# FPGA_PWR.net
KiCad netlist of a schematic drawn in Altium Designer
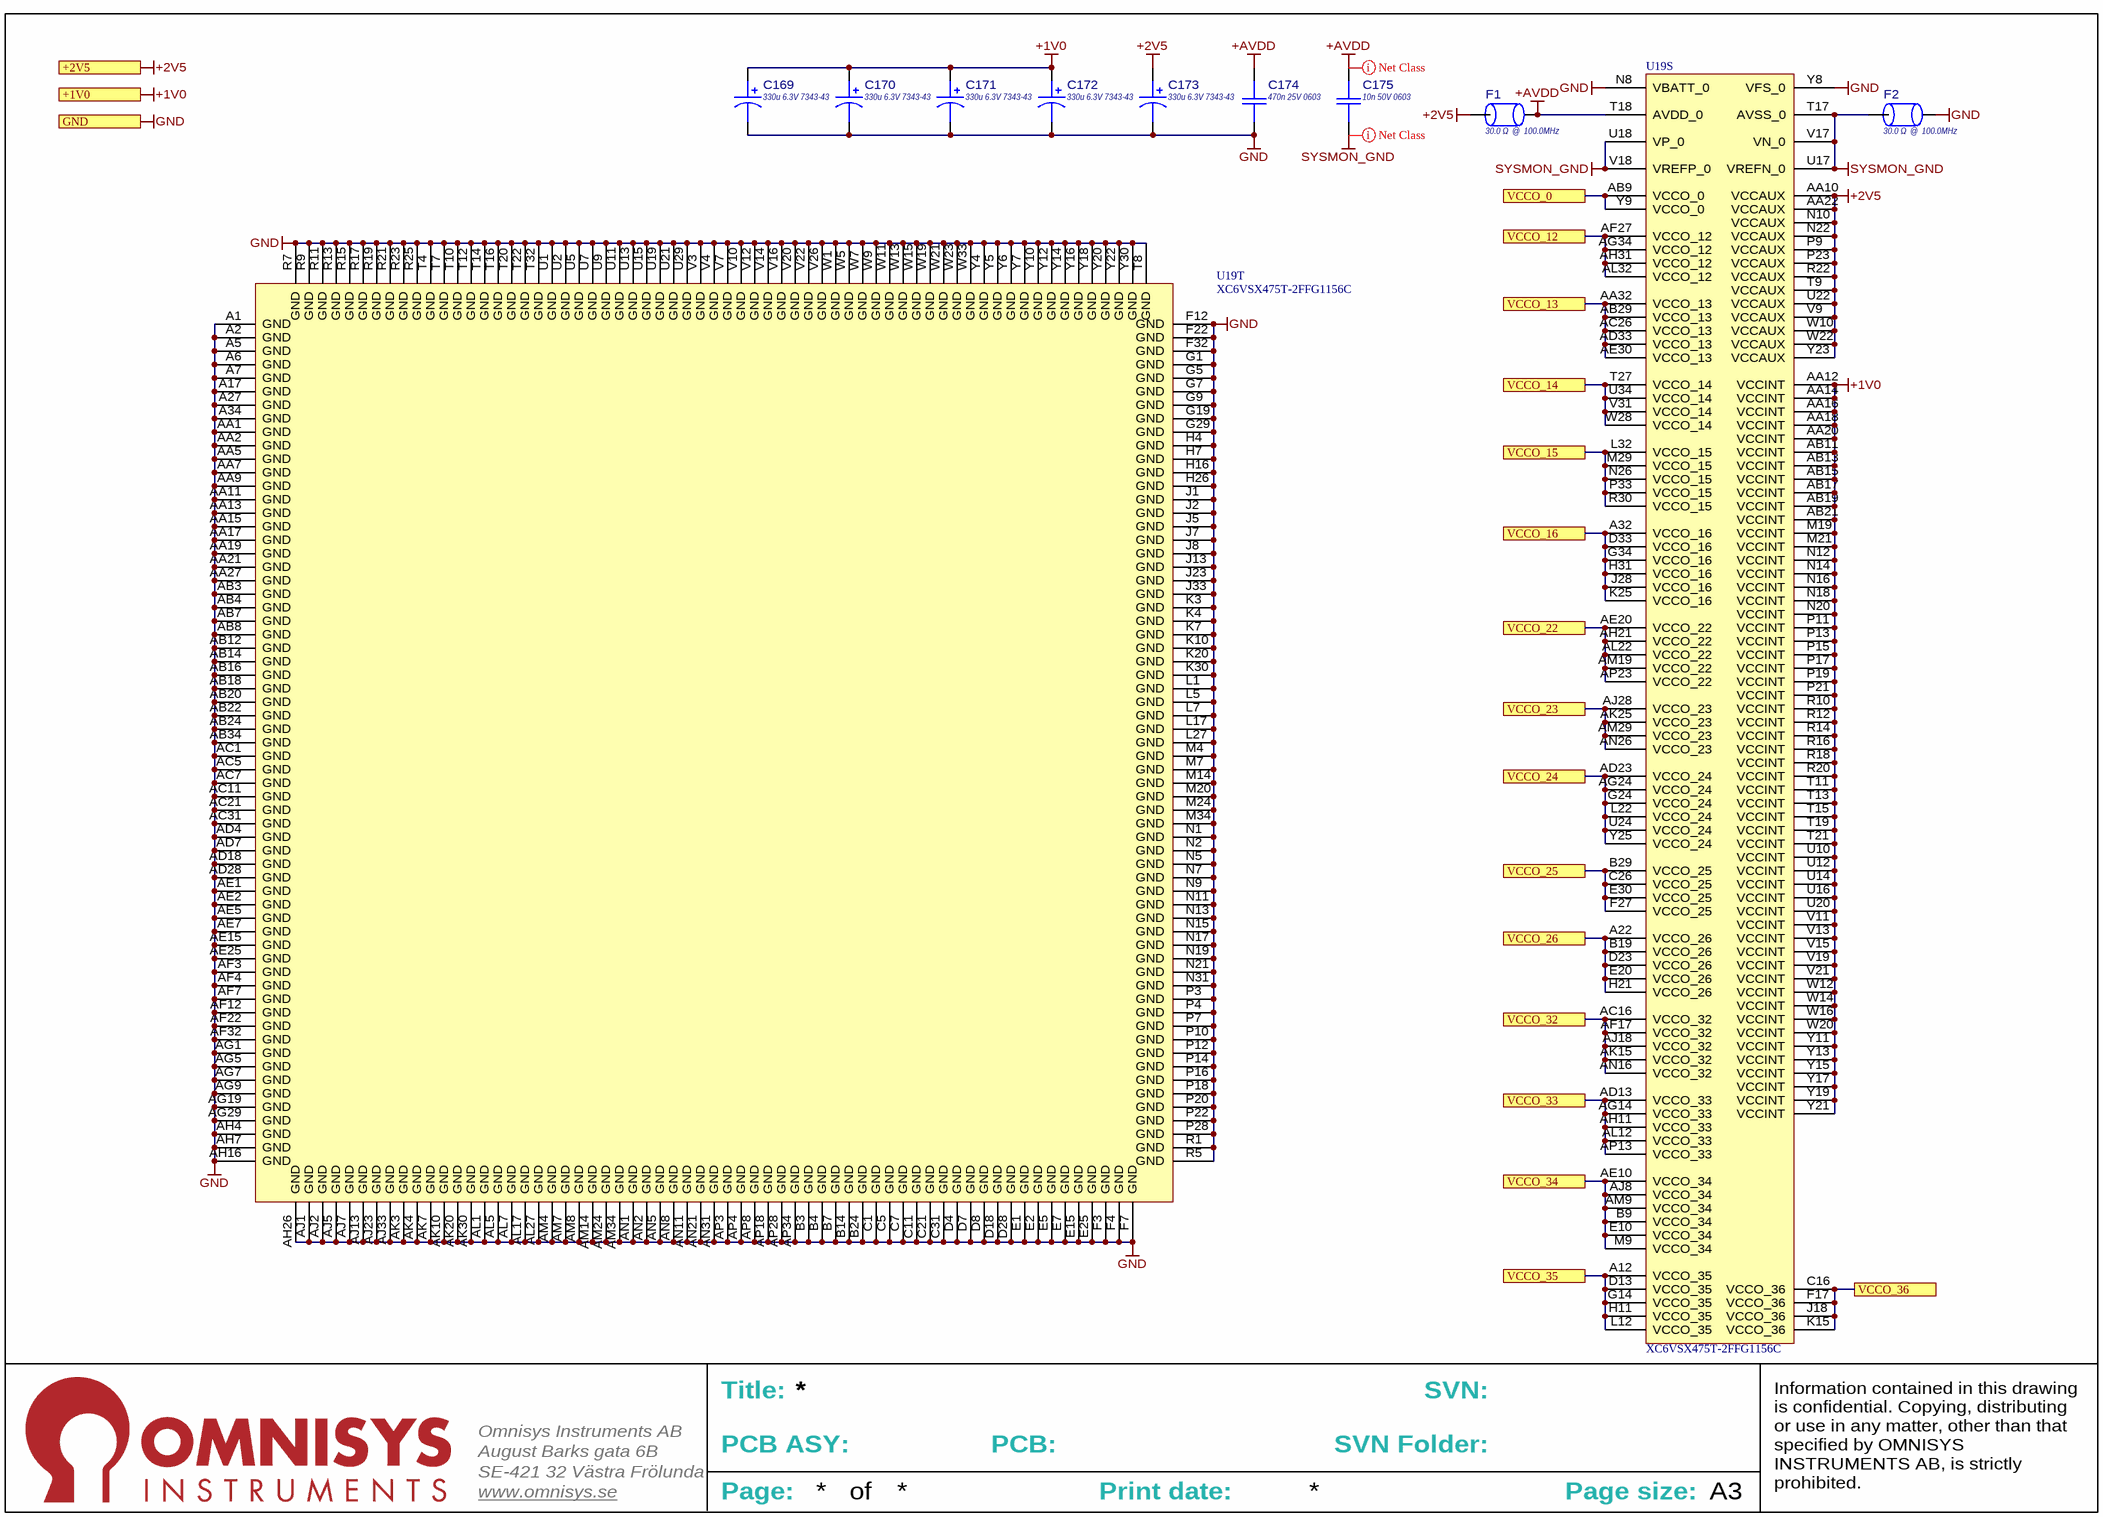
[diagram p0: FPGA_PWR.SchDoc]

(export (version "E")
  (design (tool "Eeschema 10.0.6"))
  (components
    (comp (ref "C169")
      (value "330u 6.3V 7343-43")
      (footprint "CAPMP7343X43N")
      (fields (field (name "PARTNUMBER") "NOJE337M006RWJ") (field (name "TOLERANCE") "±20%"))
      (libsource (lib "Omnisys Vault") (part "CAP-2PIN-POL"))
    )
    (comp (ref "C170")
      (value "330u 6.3V 7343-43")
      (footprint "CAPMP7343X43N")
      (fields (field (name "PARTNUMBER") "NOJE337M006RWJ") (field (name "TOLERANCE") "±20%"))
      (libsource (lib "Omnisys Vault") (part "CAP-2PIN-POL"))
    )
    (comp (ref "C171")
      (value "330u 6.3V 7343-43")
      (footprint "CAPMP7343X43N")
      (fields (field (name "PARTNUMBER") "NOJE337M006RWJ") (field (name "TOLERANCE") "±20%"))
      (libsource (lib "Omnisys Vault") (part "CAP-2PIN-POL"))
    )
    (comp (ref "C172")
      (value "330u 6.3V 7343-43")
      (footprint "CAPMP7343X43N")
      (fields (field (name "PARTNUMBER") "NOJE337M006RWJ") (field (name "TOLERANCE") "±20%"))
      (libsource (lib "Omnisys Vault") (part "CAP-2PIN-POL"))
    )
    (comp (ref "C173")
      (value "330u 6.3V 7343-43")
      (footprint "CAPMP7343X43N")
      (fields (field (name "PARTNUMBER") "NOJE337M006RWJ") (field (name "TOLERANCE") "±20%"))
      (libsource (lib "Omnisys Vault") (part "CAP-2PIN-POL"))
    )
    (comp (ref "C174")
      (value "470n 25V 0603")
      (footprint "CAPC1608X90N")
      (description "470n 25V X7R ±10% 0603 (1608 metric)")
      (fields (field (name "PARTNUMBER") "GRM188R71E474KA12") (field (name "TOLERANCE") "±10%"))
      (libsource (lib "Omnisys Vault") (part "CAP-2PIN"))
    )
    (comp (ref "C175")
      (value "10n 50V 0603")
      (footprint "CAPC1608X90N")
      (description "10n 50V X7R ±5% 0603 (1608 metric)")
      (fields (field (name "PARTNUMBER") "GRM188R71H103JA01") (field (name "TOLERANCE") "±5%"))
      (libsource (lib "Omnisys Vault") (part "CAP-2PIN"))
    )
    (comp (ref "F1")
      (value "30.0 Ω  @  100.0MHz")
      (footprint "INDC2012X11L")
      (description "Ferrite bead, Würth Elektronik WE-CBF 2012 (0805), 74279206 ,  30.0 Ω  @  100.0MHz")
      (fields (field (name "PARTNUMBER") "74279206"))
      (libsource (lib "Omnisys Vault") (part "BEAD-2PIN"))
    )
    (comp (ref "F2")
      (value "30.0 Ω  @  100.0MHz")
      (footprint "INDC2012X11L")
      (description "Ferrite bead, Würth Elektronik WE-CBF 2012 (0805), 74279206 ,  30.0 Ω  @  100.0MHz")
      (fields (field (name "PARTNUMBER") "74279206"))
      (libsource (lib "Omnisys Vault") (part "BEAD-2PIN"))
    )
    (comp (ref "U19")
      (value "XC6VSX475T-2FFG1156C")
      (footprint "FFG1156")
      (libsource (lib "Altium Content Vault") (part "FPGA-XVR6-XC6VXXXXXT-GA1156"))
    )
  )
  (nets
    (net (code "1") (name "+1V0") (class "Default")
      (node (ref "C169") (pin "1") (pinfunction "1_1") (pintype "passive"))
      (node (ref "C170") (pin "1") (pinfunction "1_1") (pintype "passive"))
      (node (ref "C171") (pin "1") (pinfunction "1_1") (pintype "passive"))
      (node (ref "C172") (pin "1") (pinfunction "1_1") (pintype "passive"))
      (node (ref "U19") (pin "AA12") (pinfunction "VCCINT_AA12") (pintype "power_in"))
      (node (ref "U19") (pin "AA14") (pinfunction "VCCINT_AA14") (pintype "power_in"))
      (node (ref "U19") (pin "AA16") (pinfunction "VCCINT_AA16") (pintype "power_in"))
      (node (ref "U19") (pin "AA18") (pinfunction "VCCINT_AA18") (pintype "power_in"))
      (node (ref "U19") (pin "AA20") (pinfunction "VCCINT_AA20") (pintype "power_in"))
      (node (ref "U19") (pin "AB11") (pinfunction "VCCINT_AB11") (pintype "power_in"))
      (node (ref "U19") (pin "AB13") (pinfunction "VCCINT_AB13") (pintype "power_in"))
      (node (ref "U19") (pin "AB15") (pinfunction "VCCINT_AB15") (pintype "power_in"))
      (node (ref "U19") (pin "AB17") (pinfunction "VCCINT_AB17") (pintype "power_in"))
      (node (ref "U19") (pin "AB19") (pinfunction "VCCINT_AB19") (pintype "power_in"))
      (node (ref "U19") (pin "AB21") (pinfunction "VCCINT_AB21") (pintype "power_in"))
      (node (ref "U19") (pin "M19") (pinfunction "VCCINT_M19") (pintype "power_in"))
      (node (ref "U19") (pin "M21") (pinfunction "VCCINT_M21") (pintype "power_in"))
      (node (ref "U19") (pin "N12") (pinfunction "VCCINT_N12") (pintype "power_in"))
      (node (ref "U19") (pin "N14") (pinfunction "VCCINT_N14") (pintype "power_in"))
      (node (ref "U19") (pin "N16") (pinfunction "VCCINT_N16") (pintype "power_in"))
      (node (ref "U19") (pin "N18") (pinfunction "VCCINT_N18") (pintype "power_in"))
      (node (ref "U19") (pin "N20") (pinfunction "VCCINT_N20") (pintype "power_in"))
      (node (ref "U19") (pin "P11") (pinfunction "VCCINT_P11") (pintype "power_in"))
      (node (ref "U19") (pin "P13") (pinfunction "VCCINT_P13") (pintype "power_in"))
      (node (ref "U19") (pin "P15") (pinfunction "VCCINT_P15") (pintype "power_in"))
      (node (ref "U19") (pin "P17") (pinfunction "VCCINT_P17") (pintype "power_in"))
      (node (ref "U19") (pin "P19") (pinfunction "VCCINT_P19") (pintype "power_in"))
      (node (ref "U19") (pin "P21") (pinfunction "VCCINT_P21") (pintype "power_in"))
      (node (ref "U19") (pin "R10") (pinfunction "VCCINT_R10") (pintype "power_in"))
      (node (ref "U19") (pin "R12") (pinfunction "VCCINT_R12") (pintype "power_in"))
      (node (ref "U19") (pin "R14") (pinfunction "VCCINT_R14") (pintype "power_in"))
      (node (ref "U19") (pin "R16") (pinfunction "VCCINT_R16") (pintype "power_in"))
      (node (ref "U19") (pin "R18") (pinfunction "VCCINT_R18") (pintype "power_in"))
      (node (ref "U19") (pin "R20") (pinfunction "VCCINT_R20") (pintype "power_in"))
      (node (ref "U19") (pin "T11") (pinfunction "VCCINT_T11") (pintype "power_in"))
      (node (ref "U19") (pin "T13") (pinfunction "VCCINT_T13") (pintype "power_in"))
      (node (ref "U19") (pin "T15") (pinfunction "VCCINT_T15") (pintype "power_in"))
      (node (ref "U19") (pin "T19") (pinfunction "VCCINT_T19") (pintype "power_in"))
      (node (ref "U19") (pin "T21") (pinfunction "VCCINT_T21") (pintype "power_in"))
      (node (ref "U19") (pin "U10") (pinfunction "VCCINT_U10") (pintype "power_in"))
      (node (ref "U19") (pin "U12") (pinfunction "VCCINT_U12") (pintype "power_in"))
      (node (ref "U19") (pin "U14") (pinfunction "VCCINT_U14") (pintype "power_in"))
      (node (ref "U19") (pin "U16") (pinfunction "VCCINT_U16") (pintype "power_in"))
      (node (ref "U19") (pin "U20") (pinfunction "VCCINT_U20") (pintype "power_in"))
      (node (ref "U19") (pin "V11") (pinfunction "VCCINT_V11") (pintype "power_in"))
      (node (ref "U19") (pin "V13") (pinfunction "VCCINT_V13") (pintype "power_in"))
      (node (ref "U19") (pin "V15") (pinfunction "VCCINT_V15") (pintype "power_in"))
      (node (ref "U19") (pin "V19") (pinfunction "VCCINT_V19") (pintype "power_in"))
      (node (ref "U19") (pin "V21") (pinfunction "VCCINT_V21") (pintype "power_in"))
      (node (ref "U19") (pin "W12") (pinfunction "VCCINT_W12") (pintype "power_in"))
      (node (ref "U19") (pin "W14") (pinfunction "VCCINT_W14") (pintype "power_in"))
      (node (ref "U19") (pin "W16") (pinfunction "VCCINT_W16") (pintype "power_in"))
      (node (ref "U19") (pin "W20") (pinfunction "VCCINT_W20") (pintype "power_in"))
      (node (ref "U19") (pin "Y11") (pinfunction "VCCINT_Y11") (pintype "power_in"))
      (node (ref "U19") (pin "Y13") (pinfunction "VCCINT_Y13") (pintype "power_in"))
      (node (ref "U19") (pin "Y15") (pinfunction "VCCINT_Y15") (pintype "power_in"))
      (node (ref "U19") (pin "Y17") (pinfunction "VCCINT_Y17") (pintype "power_in"))
      (node (ref "U19") (pin "Y19") (pinfunction "VCCINT_Y19") (pintype "power_in"))
      (node (ref "U19") (pin "Y21") (pinfunction "VCCINT_Y21") (pintype "power_in"))
    )
    (net (code "2") (name "+2V5") (class "Default")
      (node (ref "C173") (pin "1") (pinfunction "1_1") (pintype "passive"))
      (node (ref "F1") (pin "1") (pinfunction "1_1") (pintype "passive"))
      (node (ref "U19") (pin "AA10") (pinfunction "VCCAUX_AA10") (pintype "power_in"))
      (node (ref "U19") (pin "AA22") (pinfunction "VCCAUX_AA22") (pintype "power_in"))
      (node (ref "U19") (pin "N10") (pinfunction "VCCAUX_N10") (pintype "power_in"))
      (node (ref "U19") (pin "N22") (pinfunction "VCCAUX_N22") (pintype "power_in"))
      (node (ref "U19") (pin "P23") (pinfunction "VCCAUX_P23") (pintype "power_in"))
      (node (ref "U19") (pin "P9") (pinfunction "VCCAUX_P9") (pintype "power_in"))
      (node (ref "U19") (pin "R22") (pinfunction "VCCAUX_R22") (pintype "power_in"))
      (node (ref "U19") (pin "T9") (pinfunction "VCCAUX_T9") (pintype "power_in"))
      (node (ref "U19") (pin "U22") (pinfunction "VCCAUX_U22") (pintype "power_in"))
      (node (ref "U19") (pin "V9") (pinfunction "VCCAUX_V9") (pintype "power_in"))
      (node (ref "U19") (pin "W10") (pinfunction "VCCAUX_W10") (pintype "power_in"))
      (node (ref "U19") (pin "W22") (pinfunction "VCCAUX_W22") (pintype "power_in"))
      (node (ref "U19") (pin "Y23") (pinfunction "VCCAUX_Y23") (pintype "power_in"))
    )
    (net (code "3") (name "+AVDD") (class "Default")
      (node (ref "C174") (pin "1") (pinfunction "1_1") (pintype "passive"))
      (node (ref "C175") (pin "1") (pinfunction "1_1") (pintype "passive"))
      (node (ref "F1") (pin "2") (pinfunction "2_2") (pintype "passive"))
      (node (ref "U19") (pin "T18") (pinfunction "AVDD_0_T18") (pintype "power_in"))
    )
    (net (code "4") (name "/VCCO_0") (class "Default")
      (node (ref "U19") (pin "AB9") (pinfunction "VCCO_0_AB9") (pintype "power_in"))
      (node (ref "U19") (pin "Y9") (pinfunction "VCCO_0_Y9") (pintype "power_in"))
    )
    (net (code "5") (name "/VCCO_12") (class "Default")
      (node (ref "U19") (pin "AF27") (pinfunction "VCCO_12_AF27") (pintype "power_in"))
      (node (ref "U19") (pin "AG34") (pinfunction "VCCO_12_AG34") (pintype "power_in"))
      (node (ref "U19") (pin "AH31") (pinfunction "VCCO_12_AH31") (pintype "power_in"))
      (node (ref "U19") (pin "AL32") (pinfunction "VCCO_12_AL32") (pintype "power_in"))
    )
    (net (code "6") (name "/VCCO_13") (class "Default")
      (node (ref "U19") (pin "AA32") (pinfunction "VCCO_13_AA32") (pintype "power_in"))
      (node (ref "U19") (pin "AB29") (pinfunction "VCCO_13_AB29") (pintype "power_in"))
      (node (ref "U19") (pin "AC26") (pinfunction "VCCO_13_AC26") (pintype "power_in"))
      (node (ref "U19") (pin "AD33") (pinfunction "VCCO_13_AD33") (pintype "power_in"))
      (node (ref "U19") (pin "AE30") (pinfunction "VCCO_13_AE30") (pintype "power_in"))
    )
    (net (code "7") (name "/VCCO_14") (class "Default")
      (node (ref "U19") (pin "T27") (pinfunction "VCCO_14_T27") (pintype "power_in"))
      (node (ref "U19") (pin "U34") (pinfunction "VCCO_14_U34") (pintype "power_in"))
      (node (ref "U19") (pin "V31") (pinfunction "VCCO_14_V31") (pintype "power_in"))
      (node (ref "U19") (pin "W28") (pinfunction "VCCO_14_W28") (pintype "power_in"))
    )
    (net (code "8") (name "/VCCO_15") (class "Default")
      (node (ref "U19") (pin "L32") (pinfunction "VCCO_15_L32") (pintype "power_in"))
      (node (ref "U19") (pin "M29") (pinfunction "VCCO_15_M29") (pintype "power_in"))
      (node (ref "U19") (pin "N26") (pinfunction "VCCO_15_N26") (pintype "power_in"))
      (node (ref "U19") (pin "P33") (pinfunction "VCCO_15_P33") (pintype "power_in"))
      (node (ref "U19") (pin "R30") (pinfunction "VCCO_15_R30") (pintype "power_in"))
    )
    (net (code "9") (name "/VCCO_16") (class "Default")
      (node (ref "U19") (pin "A32") (pinfunction "VCCO_16_A32") (pintype "power_in"))
      (node (ref "U19") (pin "D33") (pinfunction "VCCO_16_D33") (pintype "power_in"))
      (node (ref "U19") (pin "G34") (pinfunction "VCCO_16_G34") (pintype "power_in"))
      (node (ref "U19") (pin "H31") (pinfunction "VCCO_16_H31") (pintype "power_in"))
      (node (ref "U19") (pin "J28") (pinfunction "VCCO_16_J28") (pintype "power_in"))
      (node (ref "U19") (pin "K25") (pinfunction "VCCO_16_K25") (pintype "power_in"))
    )
    (net (code "10") (name "/VCCO_22") (class "Default")
      (node (ref "U19") (pin "AE20") (pinfunction "VCCO_22_AE20") (pintype "power_in"))
      (node (ref "U19") (pin "AH21") (pinfunction "VCCO_22_AH21") (pintype "power_in"))
      (node (ref "U19") (pin "AL22") (pinfunction "VCCO_22_AL22") (pintype "power_in"))
      (node (ref "U19") (pin "AM19") (pinfunction "VCCO_22_AM19") (pintype "power_in"))
      (node (ref "U19") (pin "AP23") (pinfunction "VCCO_22_AP23") (pintype "power_in"))
    )
    (net (code "11") (name "/VCCO_23") (class "Default")
      (node (ref "U19") (pin "AJ28") (pinfunction "VCCO_23_AJ28") (pintype "power_in"))
      (node (ref "U19") (pin "AK25") (pinfunction "VCCO_23_AK25") (pintype "power_in"))
      (node (ref "U19") (pin "AM29") (pinfunction "VCCO_23_AM29") (pintype "power_in"))
      (node (ref "U19") (pin "AN26") (pinfunction "VCCO_23_AN26") (pintype "power_in"))
    )
    (net (code "12") (name "/VCCO_24") (class "Default")
      (node (ref "U19") (pin "AD23") (pinfunction "VCCO_24_AD23") (pintype "power_in"))
      (node (ref "U19") (pin "AG24") (pinfunction "VCCO_24_AG24") (pintype "power_in"))
      (node (ref "U19") (pin "G24") (pinfunction "VCCO_24_G24") (pintype "power_in"))
      (node (ref "U19") (pin "L22") (pinfunction "VCCO_24_L22") (pintype "power_in"))
      (node (ref "U19") (pin "U24") (pinfunction "VCCO_24_U24") (pintype "power_in"))
      (node (ref "U19") (pin "Y25") (pinfunction "VCCO_24_Y25") (pintype "power_in"))
    )
    (net (code "13") (name "/VCCO_25") (class "Default")
      (node (ref "U19") (pin "B29") (pinfunction "VCCO_25_B29") (pintype "power_in"))
      (node (ref "U19") (pin "C26") (pinfunction "VCCO_25_C26") (pintype "power_in"))
      (node (ref "U19") (pin "E30") (pinfunction "VCCO_25_E30") (pintype "power_in"))
      (node (ref "U19") (pin "F27") (pinfunction "VCCO_25_F27") (pintype "power_in"))
    )
    (net (code "14") (name "/VCCO_26") (class "Default")
      (node (ref "U19") (pin "A22") (pinfunction "VCCO_26_A22") (pintype "power_in"))
      (node (ref "U19") (pin "B19") (pinfunction "VCCO_26_B19") (pintype "power_in"))
      (node (ref "U19") (pin "D23") (pinfunction "VCCO_26_D23") (pintype "power_in"))
      (node (ref "U19") (pin "E20") (pinfunction "VCCO_26_E20") (pintype "power_in"))
      (node (ref "U19") (pin "H21") (pinfunction "VCCO_26_H21") (pintype "power_in"))
    )
    (net (code "15") (name "/VCCO_32") (class "Default")
      (node (ref "U19") (pin "AC16") (pinfunction "VCCO_32_AC16") (pintype "power_in"))
      (node (ref "U19") (pin "AF17") (pinfunction "VCCO_32_AF17") (pintype "power_in"))
      (node (ref "U19") (pin "AJ18") (pinfunction "VCCO_32_AJ18") (pintype "power_in"))
      (node (ref "U19") (pin "AK15") (pinfunction "VCCO_32_AK15") (pintype "power_in"))
      (node (ref "U19") (pin "AN16") (pinfunction "VCCO_32_AN16") (pintype "power_in"))
    )
    (net (code "16") (name "/VCCO_33") (class "Default")
      (node (ref "U19") (pin "AD13") (pinfunction "VCCO_33_AD13") (pintype "power_in"))
      (node (ref "U19") (pin "AG14") (pinfunction "VCCO_33_AG14") (pintype "power_in"))
      (node (ref "U19") (pin "AH11") (pinfunction "VCCO_33_AH11") (pintype "power_in"))
      (node (ref "U19") (pin "AL12") (pinfunction "VCCO_33_AL12") (pintype "power_in"))
      (node (ref "U19") (pin "AP13") (pinfunction "VCCO_33_AP13") (pintype "power_in"))
    )
    (net (code "17") (name "/VCCO_34") (class "Default")
      (node (ref "U19") (pin "AE10") (pinfunction "VCCO_34_AE10") (pintype "power_in"))
      (node (ref "U19") (pin "AJ8") (pinfunction "VCCO_34_AJ8") (pintype "power_in"))
      (node (ref "U19") (pin "AM9") (pinfunction "VCCO_34_AM9") (pintype "power_in"))
      (node (ref "U19") (pin "B9") (pinfunction "VCCO_34_B9") (pintype "power_in"))
      (node (ref "U19") (pin "E10") (pinfunction "VCCO_34_E10") (pintype "power_in"))
      (node (ref "U19") (pin "M9") (pinfunction "VCCO_34_M9") (pintype "power_in"))
    )
    (net (code "18") (name "/VCCO_35") (class "Default")
      (node (ref "U19") (pin "A12") (pinfunction "VCCO_35_A12") (pintype "power_in"))
      (node (ref "U19") (pin "D13") (pinfunction "VCCO_35_D13") (pintype "power_in"))
      (node (ref "U19") (pin "G14") (pinfunction "VCCO_35_G14") (pintype "power_in"))
      (node (ref "U19") (pin "H11") (pinfunction "VCCO_35_H11") (pintype "power_in"))
      (node (ref "U19") (pin "L12") (pinfunction "VCCO_35_L12") (pintype "power_in"))
    )
    (net (code "19") (name "/VCCO_36") (class "Default")
      (node (ref "U19") (pin "C16") (pinfunction "VCCO_36_C16") (pintype "power_in"))
      (node (ref "U19") (pin "F17") (pinfunction "VCCO_36_F17") (pintype "power_in"))
      (node (ref "U19") (pin "J18") (pinfunction "VCCO_36_J18") (pintype "power_in"))
      (node (ref "U19") (pin "K15") (pinfunction "VCCO_36_K15") (pintype "power_in"))
    )
    (net (code "20") (name "GND") (class "Default")
      (node (ref "C169") (pin "2") (pinfunction "2_2") (pintype "passive"))
      (node (ref "C170") (pin "2") (pinfunction "2_2") (pintype "passive"))
      (node (ref "C171") (pin "2") (pinfunction "2_2") (pintype "passive"))
      (node (ref "C172") (pin "2") (pinfunction "2_2") (pintype "passive"))
      (node (ref "C173") (pin "2") (pinfunction "2_2") (pintype "passive"))
      (node (ref "C174") (pin "2") (pinfunction "2_2") (pintype "passive"))
      (node (ref "F2") (pin "2") (pinfunction "2_2") (pintype "passive"))
      (node (ref "U19") (pin "A1") (pinfunction "GND_A1") (pintype "power_in"))
      (node (ref "U19") (pin "A17") (pinfunction "GND_A17") (pintype "power_in"))
      (node (ref "U19") (pin "A2") (pinfunction "GND_A2") (pintype "power_in"))
      (node (ref "U19") (pin "A27") (pinfunction "GND_A27") (pintype "power_in"))
      (node (ref "U19") (pin "A34") (pinfunction "GND_A34") (pintype "power_in"))
      (node (ref "U19") (pin "A5") (pinfunction "GND_A5") (pintype "power_in"))
      (node (ref "U19") (pin "A6") (pinfunction "GND_A6") (pintype "power_in"))
      (node (ref "U19") (pin "A7") (pinfunction "GND_A7") (pintype "power_in"))
      (node (ref "U19") (pin "AA1") (pinfunction "GND_AA1") (pintype "power_in"))
      (node (ref "U19") (pin "AA11") (pinfunction "GND_AA11") (pintype "power_in"))
      (node (ref "U19") (pin "AA13") (pinfunction "GND_AA13") (pintype "power_in"))
      (node (ref "U19") (pin "AA15") (pinfunction "GND_AA15") (pintype "power_in"))
      (node (ref "U19") (pin "AA17") (pinfunction "GND_AA17") (pintype "power_in"))
      (node (ref "U19") (pin "AA19") (pinfunction "GND_AA19") (pintype "power_in"))
      (node (ref "U19") (pin "AA2") (pinfunction "GND_AA2") (pintype "power_in"))
      (node (ref "U19") (pin "AA21") (pinfunction "GND_AA21") (pintype "power_in"))
      (node (ref "U19") (pin "AA27") (pinfunction "GND_AA27") (pintype "power_in"))
      (node (ref "U19") (pin "AA5") (pinfunction "GND_AA5") (pintype "power_in"))
      (node (ref "U19") (pin "AA7") (pinfunction "GND_AA7") (pintype "power_in"))
      (node (ref "U19") (pin "AA9") (pinfunction "GND_AA9") (pintype "power_in"))
      (node (ref "U19") (pin "AB12") (pinfunction "GND_AB12") (pintype "power_in"))
      (node (ref "U19") (pin "AB14") (pinfunction "GND_AB14") (pintype "power_in"))
      (node (ref "U19") (pin "AB16") (pinfunction "GND_AB16") (pintype "power_in"))
      (node (ref "U19") (pin "AB18") (pinfunction "GND_AB18") (pintype "power_in"))
      (node (ref "U19") (pin "AB20") (pinfunction "GND_AB20") (pintype "power_in"))
      (node (ref "U19") (pin "AB22") (pinfunction "GND_AB22") (pintype "power_in"))
      (node (ref "U19") (pin "AB24") (pinfunction "GND_AB24") (pintype "power_in"))
      (node (ref "U19") (pin "AB3") (pinfunction "GND_AB3") (pintype "power_in"))
      (node (ref "U19") (pin "AB34") (pinfunction "GND_AB34") (pintype "power_in"))
      (node (ref "U19") (pin "AB4") (pinfunction "GND_AB4") (pintype "power_in"))
      (node (ref "U19") (pin "AB7") (pinfunction "GND_AB7") (pintype "power_in"))
      (node (ref "U19") (pin "AB8") (pinfunction "GND_AB8") (pintype "power_in"))
      (node (ref "U19") (pin "AC1") (pinfunction "GND_AC1") (pintype "power_in"))
      (node (ref "U19") (pin "AC11") (pinfunction "GND_AC11") (pintype "power_in"))
      (node (ref "U19") (pin "AC21") (pinfunction "GND_AC21") (pintype "power_in"))
      (node (ref "U19") (pin "AC31") (pinfunction "GND_AC31") (pintype "power_in"))
      (node (ref "U19") (pin "AC5") (pinfunction "GND_AC5") (pintype "power_in"))
      (node (ref "U19") (pin "AC7") (pinfunction "GND_AC7") (pintype "power_in"))
      (node (ref "U19") (pin "AD18") (pinfunction "GND_AD18") (pintype "power_in"))
      (node (ref "U19") (pin "AD28") (pinfunction "GND_AD28") (pintype "power_in"))
      (node (ref "U19") (pin "AD4") (pinfunction "GND_AD4") (pintype "power_in"))
      (node (ref "U19") (pin "AD7") (pinfunction "GND_AD7") (pintype "power_in"))
      (node (ref "U19") (pin "AE1") (pinfunction "GND_AE1") (pintype "power_in"))
      (node (ref "U19") (pin "AE15") (pinfunction "GND_AE15") (pintype "power_in"))
      (node (ref "U19") (pin "AE2") (pinfunction "GND_AE2") (pintype "power_in"))
      (node (ref "U19") (pin "AE25") (pinfunction "GND_AE25") (pintype "power_in"))
      (node (ref "U19") (pin "AE5") (pinfunction "GND_AE5") (pintype "power_in"))
      (node (ref "U19") (pin "AE7") (pinfunction "GND_AE7") (pintype "power_in"))
      (node (ref "U19") (pin "AF12") (pinfunction "GND_AF12") (pintype "power_in"))
      (node (ref "U19") (pin "AF22") (pinfunction "GND_AF22") (pintype "power_in"))
      (node (ref "U19") (pin "AF3") (pinfunction "GND_AF3") (pintype "power_in"))
      (node (ref "U19") (pin "AF32") (pinfunction "GND_AF32") (pintype "power_in"))
      (node (ref "U19") (pin "AF4") (pinfunction "GND_AF4") (pintype "power_in"))
      (node (ref "U19") (pin "AF7") (pinfunction "GND_AF7") (pintype "power_in"))
      (node (ref "U19") (pin "AG1") (pinfunction "GND_AG1") (pintype "power_in"))
      (node (ref "U19") (pin "AG19") (pinfunction "GND_AG19") (pintype "power_in"))
      (node (ref "U19") (pin "AG29") (pinfunction "GND_AG29") (pintype "power_in"))
      (node (ref "U19") (pin "AG5") (pinfunction "GND_AG5") (pintype "power_in"))
      (node (ref "U19") (pin "AG7") (pinfunction "GND_AG7") (pintype "power_in"))
      (node (ref "U19") (pin "AG9") (pinfunction "GND_AG9") (pintype "power_in"))
      (node (ref "U19") (pin "AH16") (pinfunction "GND_AH16") (pintype "power_in"))
      (node (ref "U19") (pin "AH26") (pinfunction "GND_AH26") (pintype "power_in"))
      (node (ref "U19") (pin "AH4") (pinfunction "GND_AH4") (pintype "power_in"))
      (node (ref "U19") (pin "AH7") (pinfunction "GND_AH7") (pintype "power_in"))
      (node (ref "U19") (pin "AJ1") (pinfunction "GND_AJ1") (pintype "power_in"))
      (node (ref "U19") (pin "AJ13") (pinfunction "GND_AJ13") (pintype "power_in"))
      (node (ref "U19") (pin "AJ2") (pinfunction "GND_AJ2") (pintype "power_in"))
      (node (ref "U19") (pin "AJ23") (pinfunction "GND_AJ23") (pintype "power_in"))
      (node (ref "U19") (pin "AJ33") (pinfunction "GND_AJ33") (pintype "power_in"))
      (node (ref "U19") (pin "AJ5") (pinfunction "GND_AJ5") (pintype "power_in"))
      (node (ref "U19") (pin "AJ7") (pinfunction "GND_AJ7") (pintype "power_in"))
      (node (ref "U19") (pin "AK10") (pinfunction "GND_AK10") (pintype "power_in"))
      (node (ref "U19") (pin "AK20") (pinfunction "GND_AK20") (pintype "power_in"))
      (node (ref "U19") (pin "AK3") (pinfunction "GND_AK3") (pintype "power_in"))
      (node (ref "U19") (pin "AK30") (pinfunction "GND_AK30") (pintype "power_in"))
      (node (ref "U19") (pin "AK4") (pinfunction "GND_AK4") (pintype "power_in"))
      (node (ref "U19") (pin "AK7") (pinfunction "GND_AK7") (pintype "power_in"))
      (node (ref "U19") (pin "AL1") (pinfunction "GND_AL1") (pintype "power_in"))
      (node (ref "U19") (pin "AL17") (pinfunction "GND_AL17") (pintype "power_in"))
      (node (ref "U19") (pin "AL27") (pinfunction "GND_AL27") (pintype "power_in"))
      (node (ref "U19") (pin "AL5") (pinfunction "GND_AL5") (pintype "power_in"))
      (node (ref "U19") (pin "AL7") (pinfunction "GND_AL7") (pintype "power_in"))
      (node (ref "U19") (pin "AM14") (pinfunction "GND_AM14") (pintype "power_in"))
      (node (ref "U19") (pin "AM24") (pinfunction "GND_AM24") (pintype "power_in"))
      (node (ref "U19") (pin "AM34") (pinfunction "GND_AM34") (pintype "power_in"))
      (node (ref "U19") (pin "AM4") (pinfunction "GND_AM4") (pintype "power_in"))
      (node (ref "U19") (pin "AM7") (pinfunction "GND_AM7") (pintype "power_in"))
      (node (ref "U19") (pin "AM8") (pinfunction "GND_AM8") (pintype "power_in"))
      (node (ref "U19") (pin "AN1") (pinfunction "GND_AN1") (pintype "power_in"))
      (node (ref "U19") (pin "AN11") (pinfunction "GND_AN11") (pintype "power_in"))
      (node (ref "U19") (pin "AN2") (pinfunction "GND_AN2") (pintype "power_in"))
      (node (ref "U19") (pin "AN21") (pinfunction "GND_AN21") (pintype "power_in"))
      (node (ref "U19") (pin "AN31") (pinfunction "GND_AN31") (pintype "power_in"))
      (node (ref "U19") (pin "AN5") (pinfunction "GND_AN5") (pintype "power_in"))
      (node (ref "U19") (pin "AN8") (pinfunction "GND_AN8") (pintype "power_in"))
      (node (ref "U19") (pin "AP18") (pinfunction "GND_AP18") (pintype "power_in"))
      (node (ref "U19") (pin "AP28") (pinfunction "GND_AP28") (pintype "power_in"))
      (node (ref "U19") (pin "AP3") (pinfunction "GND_AP3") (pintype "power_in"))
      (node (ref "U19") (pin "AP34") (pinfunction "GND_AP34") (pintype "power_in"))
      (node (ref "U19") (pin "AP4") (pinfunction "GND_AP4") (pintype "power_in"))
      (node (ref "U19") (pin "AP8") (pinfunction "GND_AP8") (pintype "power_in"))
      (node (ref "U19") (pin "B14") (pinfunction "GND_B14") (pintype "power_in"))
      (node (ref "U19") (pin "B24") (pinfunction "GND_B24") (pintype "power_in"))
      (node (ref "U19") (pin "B3") (pinfunction "GND_B3") (pintype "power_in"))
      (node (ref "U19") (pin "B4") (pinfunction "GND_B4") (pintype "power_in"))
      (node (ref "U19") (pin "B7") (pinfunction "GND_B7") (pintype "power_in"))
      (node (ref "U19") (pin "C1") (pinfunction "GND_C1") (pintype "power_in"))
      (node (ref "U19") (pin "C11") (pinfunction "GND_C11") (pintype "power_in"))
      (node (ref "U19") (pin "C21") (pinfunction "GND_C21") (pintype "power_in"))
      (node (ref "U19") (pin "C31") (pinfunction "GND_C31") (pintype "power_in"))
      (node (ref "U19") (pin "C5") (pinfunction "GND_C5") (pintype "power_in"))
      (node (ref "U19") (pin "C7") (pinfunction "GND_C7") (pintype "power_in"))
      (node (ref "U19") (pin "D18") (pinfunction "GND_D18") (pintype "power_in"))
      (node (ref "U19") (pin "D28") (pinfunction "GND_D28") (pintype "power_in"))
      (node (ref "U19") (pin "D4") (pinfunction "GND_D4") (pintype "power_in"))
      (node (ref "U19") (pin "D7") (pinfunction "GND_D7") (pintype "power_in"))
      (node (ref "U19") (pin "D8") (pinfunction "GND_D8") (pintype "power_in"))
      (node (ref "U19") (pin "E1") (pinfunction "GND_E1") (pintype "power_in"))
      (node (ref "U19") (pin "E15") (pinfunction "GND_E15") (pintype "power_in"))
      (node (ref "U19") (pin "E2") (pinfunction "GND_E2") (pintype "power_in"))
      (node (ref "U19") (pin "E25") (pinfunction "GND_E25") (pintype "power_in"))
      (node (ref "U19") (pin "E5") (pinfunction "GND_E5") (pintype "power_in"))
      (node (ref "U19") (pin "E7") (pinfunction "GND_E7") (pintype "power_in"))
      (node (ref "U19") (pin "F12") (pinfunction "GND_F12") (pintype "power_in"))
      (node (ref "U19") (pin "F22") (pinfunction "GND_F22") (pintype "power_in"))
      (node (ref "U19") (pin "F3") (pinfunction "GND_F3") (pintype "power_in"))
      (node (ref "U19") (pin "F32") (pinfunction "GND_F32") (pintype "power_in"))
      (node (ref "U19") (pin "F4") (pinfunction "GND_F4") (pintype "power_in"))
      (node (ref "U19") (pin "F7") (pinfunction "GND_F7") (pintype "power_in"))
      (node (ref "U19") (pin "G1") (pinfunction "GND_G1") (pintype "power_in"))
      (node (ref "U19") (pin "G19") (pinfunction "GND_G19") (pintype "power_in"))
      (node (ref "U19") (pin "G29") (pinfunction "GND_G29") (pintype "power_in"))
      (node (ref "U19") (pin "G5") (pinfunction "GND_G5") (pintype "power_in"))
      (node (ref "U19") (pin "G7") (pinfunction "GND_G7") (pintype "power_in"))
      (node (ref "U19") (pin "G9") (pinfunction "GND_G9") (pintype "power_in"))
      (node (ref "U19") (pin "H16") (pinfunction "GND_H16") (pintype "power_in"))
      (node (ref "U19") (pin "H26") (pinfunction "GND_H26") (pintype "power_in"))
      (node (ref "U19") (pin "H4") (pinfunction "GND_H4") (pintype "power_in"))
      (node (ref "U19") (pin "H7") (pinfunction "GND_H7") (pintype "power_in"))
      (node (ref "U19") (pin "J1") (pinfunction "GND_J1") (pintype "power_in"))
      (node (ref "U19") (pin "J13") (pinfunction "GND_J13") (pintype "power_in"))
      (node (ref "U19") (pin "J2") (pinfunction "GND_J2") (pintype "power_in"))
      (node (ref "U19") (pin "J23") (pinfunction "GND_J23") (pintype "power_in"))
      (node (ref "U19") (pin "J33") (pinfunction "GND_J33") (pintype "power_in"))
      (node (ref "U19") (pin "J5") (pinfunction "GND_J5") (pintype "power_in"))
      (node (ref "U19") (pin "J7") (pinfunction "GND_J7") (pintype "power_in"))
      (node (ref "U19") (pin "J8") (pinfunction "GND_J8") (pintype "power_in"))
      (node (ref "U19") (pin "K10") (pinfunction "GND_K10") (pintype "power_in"))
      (node (ref "U19") (pin "K20") (pinfunction "GND_K20") (pintype "power_in"))
      (node (ref "U19") (pin "K3") (pinfunction "GND_K3") (pintype "power_in"))
      (node (ref "U19") (pin "K30") (pinfunction "GND_K30") (pintype "power_in"))
      (node (ref "U19") (pin "K4") (pinfunction "GND_K4") (pintype "power_in"))
      (node (ref "U19") (pin "K7") (pinfunction "GND_K7") (pintype "power_in"))
      (node (ref "U19") (pin "L1") (pinfunction "GND_L1") (pintype "power_in"))
      (node (ref "U19") (pin "L17") (pinfunction "GND_L17") (pintype "power_in"))
      (node (ref "U19") (pin "L27") (pinfunction "GND_L27") (pintype "power_in"))
      (node (ref "U19") (pin "L5") (pinfunction "GND_L5") (pintype "power_in"))
      (node (ref "U19") (pin "L7") (pinfunction "GND_L7") (pintype "power_in"))
      (node (ref "U19") (pin "M14") (pinfunction "GND_M14") (pintype "power_in"))
      (node (ref "U19") (pin "M20") (pinfunction "GND_M20") (pintype "power_in"))
      (node (ref "U19") (pin "M24") (pinfunction "GND_M24") (pintype "power_in"))
      (node (ref "U19") (pin "M34") (pinfunction "GND_M34") (pintype "power_in"))
      (node (ref "U19") (pin "M4") (pinfunction "GND_M4") (pintype "power_in"))
      (node (ref "U19") (pin "M7") (pinfunction "GND_M7") (pintype "power_in"))
      (node (ref "U19") (pin "N1") (pinfunction "GND_N1") (pintype "power_in"))
      (node (ref "U19") (pin "N11") (pinfunction "GND_N11") (pintype "power_in"))
      (node (ref "U19") (pin "N13") (pinfunction "GND_N13") (pintype "power_in"))
      (node (ref "U19") (pin "N15") (pinfunction "GND_N15") (pintype "power_in"))
      (node (ref "U19") (pin "N17") (pinfunction "GND_N17") (pintype "power_in"))
      (node (ref "U19") (pin "N19") (pinfunction "GND_N19") (pintype "power_in"))
      (node (ref "U19") (pin "N2") (pinfunction "GND_N2") (pintype "power_in"))
      (node (ref "U19") (pin "N21") (pinfunction "GND_N21") (pintype "power_in"))
      (node (ref "U19") (pin "N31") (pinfunction "GND_N31") (pintype "power_in"))
      (node (ref "U19") (pin "N5") (pinfunction "GND_N5") (pintype "power_in"))
      (node (ref "U19") (pin "N7") (pinfunction "GND_N7") (pintype "power_in"))
      (node (ref "U19") (pin "N8") (pinfunction "VBATT_0_N8") (pintype "power_in"))
      (node (ref "U19") (pin "N9") (pinfunction "GND_N9") (pintype "power_in"))
      (node (ref "U19") (pin "P10") (pinfunction "GND_P10") (pintype "power_in"))
      (node (ref "U19") (pin "P12") (pinfunction "GND_P12") (pintype "power_in"))
      (node (ref "U19") (pin "P14") (pinfunction "GND_P14") (pintype "power_in"))
      (node (ref "U19") (pin "P16") (pinfunction "GND_P16") (pintype "power_in"))
      (node (ref "U19") (pin "P18") (pinfunction "GND_P18") (pintype "power_in"))
      (node (ref "U19") (pin "P20") (pinfunction "GND_P20") (pintype "power_in"))
      (node (ref "U19") (pin "P22") (pinfunction "GND_P22") (pintype "power_in"))
      (node (ref "U19") (pin "P28") (pinfunction "GND_P28") (pintype "power_in"))
      (node (ref "U19") (pin "P3") (pinfunction "GND_P3") (pintype "power_in"))
      (node (ref "U19") (pin "P4") (pinfunction "GND_P4") (pintype "power_in"))
      (node (ref "U19") (pin "P7") (pinfunction "GND_P7") (pintype "power_in"))
      (node (ref "U19") (pin "R1") (pinfunction "GND_R1") (pintype "power_in"))
      (node (ref "U19") (pin "R11") (pinfunction "GND_R11") (pintype "power_in"))
      (node (ref "U19") (pin "R13") (pinfunction "GND_R13") (pintype "power_in"))
      (node (ref "U19") (pin "R15") (pinfunction "GND_R15") (pintype "power_in"))
      (node (ref "U19") (pin "R17") (pinfunction "GND_R17") (pintype "power_in"))
      (node (ref "U19") (pin "R19") (pinfunction "GND_R19") (pintype "power_in"))
      (node (ref "U19") (pin "R21") (pinfunction "GND_R21") (pintype "power_in"))
      (node (ref "U19") (pin "R23") (pinfunction "GND_R23") (pintype "power_in"))
      (node (ref "U19") (pin "R25") (pinfunction "GND_R25") (pintype "power_in"))
      (node (ref "U19") (pin "R5") (pinfunction "GND_R5") (pintype "power_in"))
      (node (ref "U19") (pin "R7") (pinfunction "GND_R7") (pintype "power_in"))
      (node (ref "U19") (pin "R9") (pinfunction "GND_R9") (pintype "power_in"))
      (node (ref "U19") (pin "T10") (pinfunction "GND_T10") (pintype "power_in"))
      (node (ref "U19") (pin "T12") (pinfunction "GND_T12") (pintype "power_in"))
      (node (ref "U19") (pin "T14") (pinfunction "GND_T14") (pintype "power_in"))
      (node (ref "U19") (pin "T16") (pinfunction "GND_T16") (pintype "power_in"))
      (node (ref "U19") (pin "T20") (pinfunction "GND_T20") (pintype "power_in"))
      (node (ref "U19") (pin "T22") (pinfunction "GND_T22") (pintype "power_in"))
      (node (ref "U19") (pin "T32") (pinfunction "GND_T32") (pintype "power_in"))
      (node (ref "U19") (pin "T4") (pinfunction "GND_T4") (pintype "power_in"))
      (node (ref "U19") (pin "T7") (pinfunction "GND_T7") (pintype "power_in"))
      (node (ref "U19") (pin "T8") (pinfunction "GND_T8") (pintype "power_in"))
      (node (ref "U19") (pin "U1") (pinfunction "GND_U1") (pintype "power_in"))
      (node (ref "U19") (pin "U11") (pinfunction "GND_U11") (pintype "power_in"))
      (node (ref "U19") (pin "U13") (pinfunction "GND_U13") (pintype "power_in"))
      (node (ref "U19") (pin "U15") (pinfunction "GND_U15") (pintype "power_in"))
      (node (ref "U19") (pin "U19") (pinfunction "GND_U19") (pintype "power_in"))
      (node (ref "U19") (pin "U2") (pinfunction "GND_U2") (pintype "power_in"))
      (node (ref "U19") (pin "U21") (pinfunction "GND_U21") (pintype "power_in"))
      (node (ref "U19") (pin "U29") (pinfunction "GND_U29") (pintype "power_in"))
      (node (ref "U19") (pin "U5") (pinfunction "GND_U5") (pintype "power_in"))
      (node (ref "U19") (pin "U7") (pinfunction "GND_U7") (pintype "power_in"))
      (node (ref "U19") (pin "U9") (pinfunction "GND_U9") (pintype "power_in"))
      (node (ref "U19") (pin "V10") (pinfunction "GND_V10") (pintype "power_in"))
      (node (ref "U19") (pin "V12") (pinfunction "GND_V12") (pintype "power_in"))
      (node (ref "U19") (pin "V14") (pinfunction "GND_V14") (pintype "power_in"))
      (node (ref "U19") (pin "V16") (pinfunction "GND_V16") (pintype "power_in"))
      (node (ref "U19") (pin "V20") (pinfunction "GND_V20") (pintype "power_in"))
      (node (ref "U19") (pin "V22") (pinfunction "GND_V22") (pintype "power_in"))
      (node (ref "U19") (pin "V26") (pinfunction "GND_V26") (pintype "power_in"))
      (node (ref "U19") (pin "V3") (pinfunction "GND_V3") (pintype "power_in"))
      (node (ref "U19") (pin "V4") (pinfunction "GND_V4") (pintype "power_in"))
      (node (ref "U19") (pin "V7") (pinfunction "GND_V7") (pintype "power_in"))
      (node (ref "U19") (pin "W1") (pinfunction "GND_W1") (pintype "power_in"))
      (node (ref "U19") (pin "W11") (pinfunction "GND_W11") (pintype "power_in"))
      (node (ref "U19") (pin "W13") (pinfunction "GND_W13") (pintype "power_in"))
      (node (ref "U19") (pin "W15") (pinfunction "GND_W15") (pintype "power_in"))
      (node (ref "U19") (pin "W19") (pinfunction "GND_W19") (pintype "power_in"))
      (node (ref "U19") (pin "W21") (pinfunction "GND_W21") (pintype "power_in"))
      (node (ref "U19") (pin "W23") (pinfunction "GND_W23") (pintype "power_in"))
      (node (ref "U19") (pin "W33") (pinfunction "GND_W33") (pintype "power_in"))
      (node (ref "U19") (pin "W5") (pinfunction "GND_W5") (pintype "power_in"))
      (node (ref "U19") (pin "W7") (pinfunction "GND_W7") (pintype "power_in"))
      (node (ref "U19") (pin "W9") (pinfunction "GND_W9") (pintype "power_in"))
      (node (ref "U19") (pin "Y10") (pinfunction "GND_Y10") (pintype "power_in"))
      (node (ref "U19") (pin "Y12") (pinfunction "GND_Y12") (pintype "power_in"))
      (node (ref "U19") (pin "Y14") (pinfunction "GND_Y14") (pintype "power_in"))
      (node (ref "U19") (pin "Y16") (pinfunction "GND_Y16") (pintype "power_in"))
      (node (ref "U19") (pin "Y18") (pinfunction "GND_Y18") (pintype "power_in"))
      (node (ref "U19") (pin "Y20") (pinfunction "GND_Y20") (pintype "power_in"))
      (node (ref "U19") (pin "Y22") (pinfunction "GND_Y22") (pintype "power_in"))
      (node (ref "U19") (pin "Y30") (pinfunction "GND_Y30") (pintype "power_in"))
      (node (ref "U19") (pin "Y4") (pinfunction "GND_Y4") (pintype "power_in"))
      (node (ref "U19") (pin "Y5") (pinfunction "GND_Y5") (pintype "power_in"))
      (node (ref "U19") (pin "Y6") (pinfunction "GND_Y6") (pintype "power_in"))
      (node (ref "U19") (pin "Y7") (pinfunction "GND_Y7") (pintype "power_in"))
      (node (ref "U19") (pin "Y8") (pinfunction "VFS_0_Y8") (pintype "power_in"))
    )
    (net (code "21") (name "SYSMON_GND") (class "Default")
      (node (ref "C175") (pin "2") (pinfunction "2_2") (pintype "passive"))
      (node (ref "F2") (pin "1") (pinfunction "1_1") (pintype "passive"))
      (node (ref "U19") (pin "T17") (pinfunction "AVSS_0_T17") (pintype "power_in"))
      (node (ref "U19") (pin "U17") (pinfunction "VREFN_0_U17") (pintype "power_in"))
      (node (ref "U19") (pin "U18") (pinfunction "VP_0_U18") (pintype "power_in"))
      (node (ref "U19") (pin "V17") (pinfunction "VN_0_V17") (pintype "power_in"))
      (node (ref "U19") (pin "V18") (pinfunction "VREFP_0_V18") (pintype "power_in"))
    )
  )
)
